# main.net
KiCad netlist of a schematic drawn in EAGLE
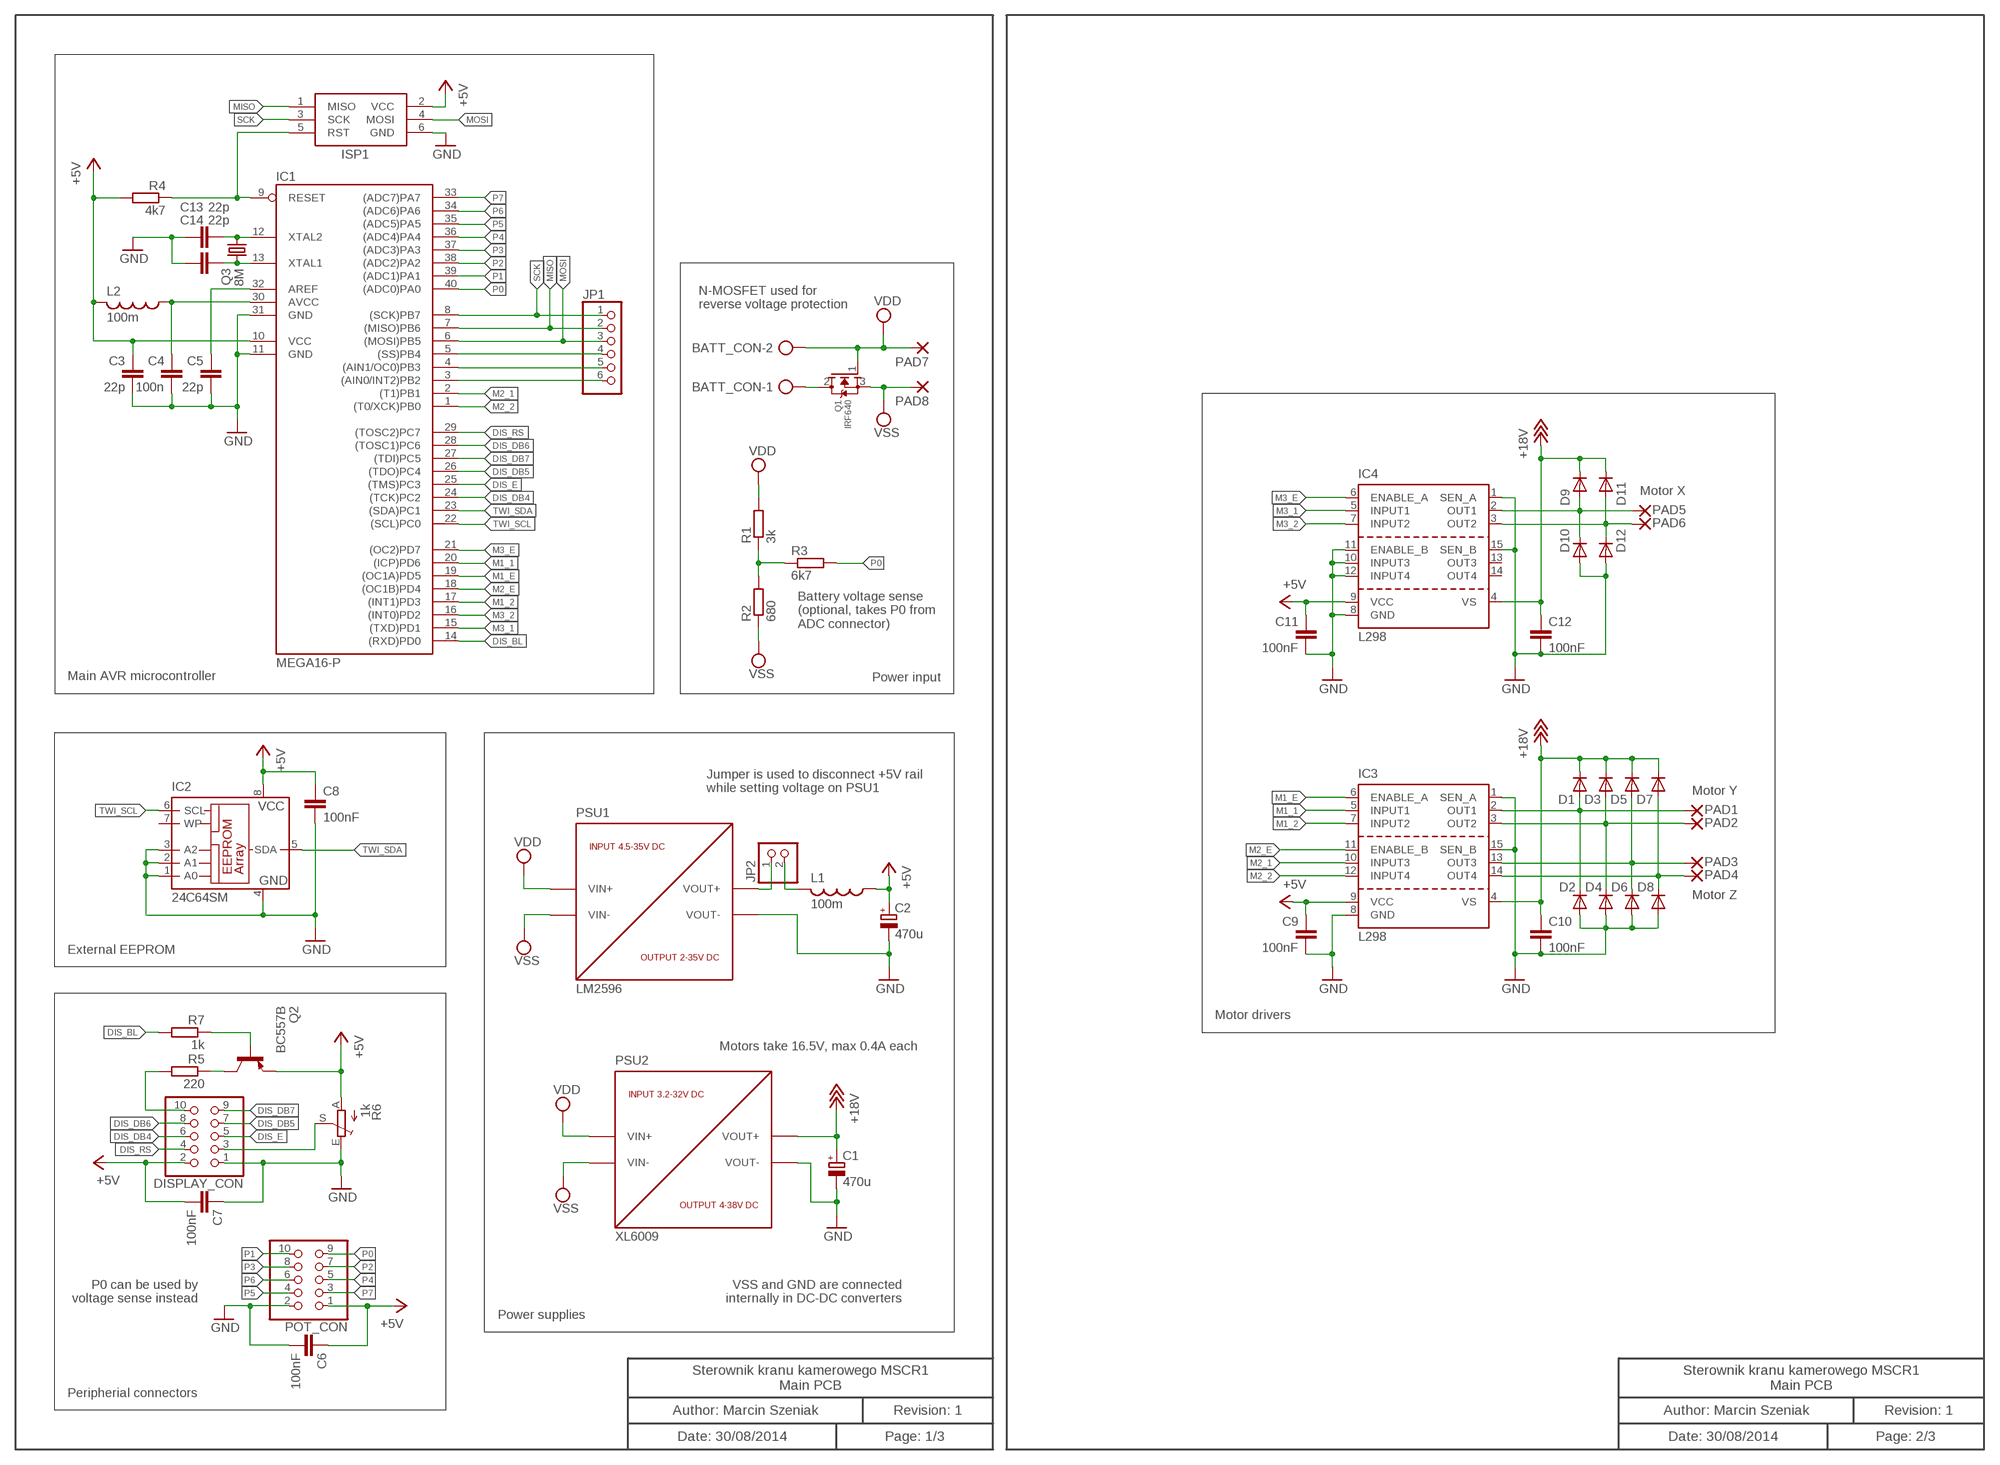
[diagram p0: schematic, sheet 1]

(export (version "E")
  (design (tool "Eeschema 10.0.6"))
  (components
    (comp (ref "BATT_CON")
      (value "AK500/2-H")
      (footprint "eagle-import:AK500_2-H")
      (libsource (lib "eagle-import") (part "AK500/2-H"))
    )
    (comp (ref "C1")
      (value "470u")
      (footprint "eagle-import:E3,5-8")
      (libsource (lib "eagle-import") (part "CPOL-EUE3.5-8"))
    )
    (comp (ref "C2")
      (value "470u")
      (footprint "eagle-import:E5-8,5")
      (libsource (lib "eagle-import") (part "CPOL-EUE5-8.5"))
    )
    (comp (ref "C3")
      (value "22p")
      (footprint "eagle-import:C025-025X050")
      (libsource (lib "eagle-import") (part "C-EU025-025X050"))
    )
    (comp (ref "C4")
      (value "100n")
      (footprint "eagle-import:C025-025X050")
      (libsource (lib "eagle-import") (part "C-EU025-025X050"))
    )
    (comp (ref "C5")
      (value "22p")
      (footprint "eagle-import:C025-025X050")
      (libsource (lib "eagle-import") (part "C-EU025-025X050"))
    )
    (comp (ref "C6")
      (value "100nF")
      (footprint "eagle-import:C025-025X050")
      (libsource (lib "eagle-import") (part "C-EU025-025X050"))
    )
    (comp (ref "C7")
      (value "100nF")
      (footprint "eagle-import:C050-024X044")
      (libsource (lib "eagle-import") (part "C-EU050-024X044"))
    )
    (comp (ref "C8")
      (value "100nF")
      (footprint "eagle-import:C050-024X044")
      (libsource (lib "eagle-import") (part "C-EU050-024X044"))
    )
    (comp (ref "C9")
      (value "100nF")
      (footprint "eagle-import:C075-032X103")
      (libsource (lib "eagle-import") (part "C-EU075-032X103"))
    )
    (comp (ref "C10")
      (value "100nF")
      (footprint "eagle-import:C075-032X103")
      (libsource (lib "eagle-import") (part "C-EU075-032X103"))
    )
    (comp (ref "C11")
      (value "100nF")
      (footprint "eagle-import:C075-032X103")
      (libsource (lib "eagle-import") (part "C-EU075-032X103"))
    )
    (comp (ref "C12")
      (value "100nF")
      (footprint "eagle-import:C075-032X103")
      (libsource (lib "eagle-import") (part "C-EU075-032X103"))
    )
    (comp (ref "C13")
      (value "22p")
      (footprint "eagle-import:C025-025X050")
      (libsource (lib "eagle-import") (part "C-EU025-025X050"))
    )
    (comp (ref "C14")
      (value "22p")
      (footprint "eagle-import:C025-025X050")
      (libsource (lib "eagle-import") (part "C-EU025-025X050"))
    )
    (comp (ref "D1")
      (value "UF4003")
      (footprint "eagle-import:DO41-10")
      (libsource (lib "eagle-import") (part "UF4003"))
    )
    (comp (ref "D2")
      (value "UF4003")
      (footprint "eagle-import:DO41-10")
      (libsource (lib "eagle-import") (part "UF4003"))
    )
    (comp (ref "D3")
      (value "UF4003")
      (footprint "eagle-import:DO41-10")
      (libsource (lib "eagle-import") (part "UF4003"))
    )
    (comp (ref "D4")
      (value "UF4003")
      (footprint "eagle-import:DO41-10")
      (libsource (lib "eagle-import") (part "UF4003"))
    )
    (comp (ref "D5")
      (value "UF4003")
      (footprint "eagle-import:DO41-10")
      (libsource (lib "eagle-import") (part "UF4003"))
    )
    (comp (ref "D6")
      (value "UF4003")
      (footprint "eagle-import:DO41-10")
      (libsource (lib "eagle-import") (part "UF4003"))
    )
    (comp (ref "D7")
      (value "UF4003")
      (footprint "eagle-import:DO41-10")
      (libsource (lib "eagle-import") (part "UF4003"))
    )
    (comp (ref "D8")
      (value "UF4003")
      (footprint "eagle-import:DO41-10")
      (libsource (lib "eagle-import") (part "UF4003"))
    )
    (comp (ref "D9")
      (value "UF4003")
      (footprint "eagle-import:DO41-10")
      (libsource (lib "eagle-import") (part "UF4003"))
    )
    (comp (ref "D10")
      (value "UF4003")
      (footprint "eagle-import:DO41-10")
      (libsource (lib "eagle-import") (part "UF4003"))
    )
    (comp (ref "D11")
      (value "UF4003")
      (footprint "eagle-import:DO41-10")
      (libsource (lib "eagle-import") (part "UF4003"))
    )
    (comp (ref "D12")
      (value "UF4003")
      (footprint "eagle-import:DO41-10")
      (libsource (lib "eagle-import") (part "UF4003"))
    )
    (comp (ref "DISPLAY_CON")
      (value "PINHD-2X5")
      (footprint "eagle-import:2X05")
      (libsource (lib "eagle-import") (part "PINHD-2X5"))
    )
    (comp (ref "IC1")
      (value "MEGA16-P")
      (footprint "eagle-import:DIL40")
      (fields (field (name "MPN") "ATMEGA16-16PU"))
      (libsource (lib "eagle-import") (part "MEGA16-P"))
    )
    (comp (ref "IC2")
      (value "24C64SM")
      (footprint "eagle-import:SO-08M")
      (fields (field (name "MF") "RAMTRON INTERNATIONAL CORP") (field (name "MPN") "FM24C64-S"))
      (libsource (lib "eagle-import") (part "24SMC64"))
    )
    (comp (ref "IC3")
      (value "L298")
      (footprint "eagle-import:MULTIWATT-15")
      (fields (field (name "MPN") "L298N"))
      (libsource (lib "eagle-import") (part "L298"))
    )
    (comp (ref "IC4")
      (value "L298")
      (footprint "eagle-import:MULTIWATT-15")
      (fields (field (name "MPN") "L298N"))
      (libsource (lib "eagle-import") (part "L298"))
    )
    (comp (ref "ISP1")
      (value "AVRISP-6")
      (footprint "eagle-import:AVRISP")
      (libsource (lib "eagle-import") (part "AVRISP-6"))
    )
    (comp (ref "JP1")
      (value "PINHD-1X6")
      (footprint "eagle-import:1X06")
      (libsource (lib "eagle-import") (part "PINHD-1X6"))
    )
    (comp (ref "JP2")
      (value "PINHD-1X2")
      (footprint "eagle-import:1X02")
      (libsource (lib "eagle-import") (part "PINHD-1X2"))
    )
    (comp (ref "L1")
      (value "100m")
      (footprint "eagle-import:0204_7")
      (libsource (lib "eagle-import") (part "L-US0204/7"))
    )
    (comp (ref "L2")
      (value "100m")
      (footprint "eagle-import:0204_7")
      (libsource (lib "eagle-import") (part "L-US0204/7"))
    )
    (comp (ref "PAD1")
      (value "2,54/1,1KLOCWIRE1")
      (footprint "eagle-import:KLOCWIRE1")
      (libsource (lib "eagle-import") (part "2,54/1,1KLOCWIRE1"))
    )
    (comp (ref "PAD2")
      (value "2,54/1,1KLOCWIRE1")
      (footprint "eagle-import:KLOCWIRE1")
      (libsource (lib "eagle-import") (part "2,54/1,1KLOCWIRE1"))
    )
    (comp (ref "PAD3")
      (value "2,54/1,1KLOCWIRE1")
      (footprint "eagle-import:KLOCWIRE1")
      (libsource (lib "eagle-import") (part "2,54/1,1KLOCWIRE1"))
    )
    (comp (ref "PAD4")
      (value "2,54/1,1KLOCWIRE1")
      (footprint "eagle-import:KLOCWIRE1")
      (libsource (lib "eagle-import") (part "2,54/1,1KLOCWIRE1"))
    )
    (comp (ref "PAD5")
      (value "2,54/1,1KLOCWIRE1")
      (footprint "eagle-import:KLOCWIRE1")
      (libsource (lib "eagle-import") (part "2,54/1,1KLOCWIRE1"))
    )
    (comp (ref "PAD6")
      (value "2,54/1,1KLOCWIRE1")
      (footprint "eagle-import:KLOCWIRE1")
      (libsource (lib "eagle-import") (part "2,54/1,1KLOCWIRE1"))
    )
    (comp (ref "PAD7")
      (value "2,54/1,1KLOCWIRE1")
      (footprint "eagle-import:KLOCWIRE1")
      (libsource (lib "eagle-import") (part "2,54/1,1KLOCWIRE1"))
    )
    (comp (ref "PAD8")
      (value "2,54/1,1KLOCWIRE1")
      (footprint "eagle-import:KLOCWIRE1")
      (libsource (lib "eagle-import") (part "2,54/1,1KLOCWIRE1"))
    )
    (comp (ref "POT_CON")
      (value "PINHD-2X5")
      (footprint "eagle-import:2X05")
      (libsource (lib "eagle-import") (part "PINHD-2X5"))
    )
    (comp (ref "PSU1")
      (value "LM2596")
      (footprint "eagle-import:DC-DC_CONV_MODULE")
      (libsource (lib "eagle-import") (part "DC-DC_CONV_DN"))
    )
    (comp (ref "PSU2")
      (value "XL6009")
      (footprint "eagle-import:DC-DC_CONV_MODULE")
      (libsource (lib "eagle-import") (part "DC-DC_CONV_UP"))
    )
    (comp (ref "Q1")
      (value "IRF640")
      (footprint "eagle-import:TO220V")
      (libsource (lib "eagle-import") (part "MOSFET-NGDS_TO220V"))
    )
    (comp (ref "Q2")
      (value "BC557B")
      (footprint "eagle-import:TO92-EBC")
      (libsource (lib "eagle-import") (part "BC557B"))
    )
    (comp (ref "Q3")
      (value "8M")
      (footprint "eagle-import:TC26V")
      (libsource (lib "eagle-import") (part "CRYSTALTC26V"))
    )
    (comp (ref "R1")
      (value "3k")
      (footprint "eagle-import:0204_7")
      (libsource (lib "eagle-import") (part "R-EU_0204/7"))
    )
    (comp (ref "R2")
      (value "680")
      (footprint "eagle-import:0204_7")
      (libsource (lib "eagle-import") (part "R-EU_0204/7"))
    )
    (comp (ref "R3")
      (value "6k7")
      (footprint "eagle-import:0204_5")
      (libsource (lib "eagle-import") (part "R-EU_0204/5"))
    )
    (comp (ref "R4")
      (value "4k7")
      (footprint "eagle-import:0204_5")
      (libsource (lib "eagle-import") (part "R-EU_0204/5"))
    )
    (comp (ref "R5")
      (value "220")
      (footprint "eagle-import:0204_7")
      (libsource (lib "eagle-import") (part "R-EU_0204/7"))
    )
    (comp (ref "R6")
      (value "1k")
      (footprint "eagle-import:CA6V")
      (libsource (lib "eagle-import") (part "TRIM_EU-CA6V"))
    )
    (comp (ref "R7")
      (value "1k")
      (footprint "eagle-import:0204_7")
      (libsource (lib "eagle-import") (part "R-EU_0204/7"))
    )
  )
  (nets
    (net (code "1") (name "+5V") (class "Default")
      (node (ref "C11") (pin "1") (pinfunction "1_1") (pintype "passive"))
      (node (ref "C2") (pin "+") (pinfunction "+_+") (pintype "passive"))
      (node (ref "C3") (pin "1") (pinfunction "1_1") (pintype "passive"))
      (node (ref "C6") (pin "1") (pinfunction "1_1") (pintype "passive"))
      (node (ref "C7") (pin "2") (pinfunction "2_2") (pintype "passive"))
      (node (ref "C8") (pin "1") (pinfunction "1_1") (pintype "passive"))
      (node (ref "C9") (pin "1") (pinfunction "1_1") (pintype "passive"))
      (node (ref "DISPLAY_CON") (pin "2") (pinfunction "2_2") (pintype "passive"))
      (node (ref "IC1") (pin "10") (pinfunction "VCC_10") (pintype "power_in"))
      (node (ref "IC2") (pin "8") (pinfunction "VCC_8") (pintype "power_in"))
      (node (ref "IC3") (pin "9") (pinfunction "VCC_9") (pintype "power_in"))
      (node (ref "IC4") (pin "9") (pinfunction "VCC_9") (pintype "power_in"))
      (node (ref "ISP1") (pin "2") (pinfunction "VCC_2") (pintype "power_in"))
      (node (ref "L1") (pin "1") (pinfunction "1_1") (pintype "passive"))
      (node (ref "L2") (pin "2") (pinfunction "2_2") (pintype "passive"))
      (node (ref "POT_CON") (pin "1") (pinfunction "1_1") (pintype "passive"))
      (node (ref "Q2") (pin "E") (pinfunction "E_E") (pintype "passive"))
      (node (ref "R4") (pin "2") (pinfunction "2_2") (pintype "passive"))
      (node (ref "R6") (pin "A") (pinfunction "A_A") (pintype "passive"))
    )
    (net (code "2") (name "+18V") (class "Default")
      (node (ref "C1") (pin "+") (pinfunction "+_+") (pintype "passive"))
      (node (ref "C10") (pin "1") (pinfunction "1_1") (pintype "passive"))
      (node (ref "C12") (pin "1") (pinfunction "1_1") (pintype "passive"))
      (node (ref "D1") (pin "C") (pinfunction "C_C") (pintype "passive"))
      (node (ref "D11") (pin "C") (pinfunction "C_C") (pintype "passive"))
      (node (ref "D3") (pin "C") (pinfunction "C_C") (pintype "passive"))
      (node (ref "D5") (pin "C") (pinfunction "C_C") (pintype "passive"))
      (node (ref "D7") (pin "C") (pinfunction "C_C") (pintype "passive"))
      (node (ref "D9") (pin "C") (pinfunction "C_C") (pintype "passive"))
      (node (ref "IC3") (pin "4") (pinfunction "VS_4") (pintype "power_in"))
      (node (ref "IC4") (pin "4") (pinfunction "VS_4") (pintype "power_in"))
      (node (ref "PSU2") (pin "OUT+") (pinfunction "VOUT+_OUT+") (pintype "power_in"))
    )
    (net (code "3") (name "DIS_BL") (class "Default")
      (node (ref "IC1") (pin "14") (pinfunction "(RXD)PD0_14") (pintype "bidirectional"))
      (node (ref "R7") (pin "2") (pinfunction "2_2") (pintype "passive"))
    )
    (net (code "4") (name "DIS_DB4") (class "Default")
      (node (ref "DISPLAY_CON") (pin "6") (pinfunction "6_6") (pintype "passive"))
      (node (ref "IC1") (pin "24") (pinfunction "(TCK)PC2_24") (pintype "bidirectional"))
    )
    (net (code "5") (name "DIS_DB5") (class "Default")
      (node (ref "DISPLAY_CON") (pin "7") (pinfunction "7_7") (pintype "passive"))
      (node (ref "IC1") (pin "26") (pinfunction "(TDO)PC4_26") (pintype "bidirectional"))
    )
    (net (code "6") (name "DIS_DB6") (class "Default")
      (node (ref "DISPLAY_CON") (pin "8") (pinfunction "8_8") (pintype "passive"))
      (node (ref "IC1") (pin "28") (pinfunction "(TOSC1)PC6_28") (pintype "bidirectional"))
    )
    (net (code "7") (name "DIS_DB7") (class "Default")
      (node (ref "DISPLAY_CON") (pin "9") (pinfunction "9_9") (pintype "passive"))
      (node (ref "IC1") (pin "27") (pinfunction "(TDI)PC5_27") (pintype "bidirectional"))
    )
    (net (code "8") (name "DIS_E") (class "Default")
      (node (ref "DISPLAY_CON") (pin "5") (pinfunction "5_5") (pintype "passive"))
      (node (ref "IC1") (pin "25") (pinfunction "(TMS)PC3_25") (pintype "bidirectional"))
    )
    (net (code "9") (name "DIS_RS") (class "Default")
      (node (ref "DISPLAY_CON") (pin "4") (pinfunction "4_4") (pintype "passive"))
      (node (ref "IC1") (pin "29") (pinfunction "(TOSC2)PC7_29") (pintype "bidirectional"))
    )
    (net (code "10") (name "GND") (class "Default")
      (node (ref "C1") (pin "-") (pinfunction "-_-") (pintype "passive"))
      (node (ref "C10") (pin "2") (pinfunction "2_2") (pintype "passive"))
      (node (ref "C11") (pin "2") (pinfunction "2_2") (pintype "passive"))
      (node (ref "C12") (pin "2") (pinfunction "2_2") (pintype "passive"))
      (node (ref "C13") (pin "2") (pinfunction "2_2") (pintype "passive"))
      (node (ref "C14") (pin "2") (pinfunction "2_2") (pintype "passive"))
      (node (ref "C2") (pin "-") (pinfunction "-_-") (pintype "passive"))
      (node (ref "C3") (pin "2") (pinfunction "2_2") (pintype "passive"))
      (node (ref "C4") (pin "2") (pinfunction "2_2") (pintype "passive"))
      (node (ref "C5") (pin "2") (pinfunction "2_2") (pintype "passive"))
      (node (ref "C6") (pin "2") (pinfunction "2_2") (pintype "passive"))
      (node (ref "C7") (pin "1") (pinfunction "1_1") (pintype "passive"))
      (node (ref "C8") (pin "2") (pinfunction "2_2") (pintype "passive"))
      (node (ref "C9") (pin "2") (pinfunction "2_2") (pintype "passive"))
      (node (ref "D10") (pin "A") (pinfunction "A_A") (pintype "passive"))
      (node (ref "D12") (pin "A") (pinfunction "A_A") (pintype "passive"))
      (node (ref "D2") (pin "A") (pinfunction "A_A") (pintype "passive"))
      (node (ref "D4") (pin "A") (pinfunction "A_A") (pintype "passive"))
      (node (ref "D6") (pin "A") (pinfunction "A_A") (pintype "passive"))
      (node (ref "D8") (pin "A") (pinfunction "A_A") (pintype "passive"))
      (node (ref "DISPLAY_CON") (pin "1") (pinfunction "1_1") (pintype "passive"))
      (node (ref "IC1") (pin "11") (pinfunction "GND_11") (pintype "power_in"))
      (node (ref "IC1") (pin "31") (pinfunction "GND_31") (pintype "power_in"))
      (node (ref "IC2") (pin "1") (pinfunction "A0_1") (pintype "input"))
      (node (ref "IC2") (pin "2") (pinfunction "A1_2") (pintype "input"))
      (node (ref "IC2") (pin "3") (pinfunction "A2_3") (pintype "input"))
      (node (ref "IC2") (pin "4") (pinfunction "GND_4") (pintype "power_in"))
      (node (ref "IC3") (pin "1") (pinfunction "SEN_A_1") (pintype "input"))
      (node (ref "IC3") (pin "15") (pinfunction "SEN_B_15") (pintype "input"))
      (node (ref "IC3") (pin "8") (pinfunction "GND_8") (pintype "power_in"))
      (node (ref "IC4") (pin "1") (pinfunction "SEN_A_1") (pintype "input"))
      (node (ref "IC4") (pin "10") (pinfunction "INPUT3_10") (pintype "input"))
      (node (ref "IC4") (pin "11") (pinfunction "ENABLE_B_11") (pintype "input"))
      (node (ref "IC4") (pin "12") (pinfunction "INPUT4_12") (pintype "input"))
      (node (ref "IC4") (pin "15") (pinfunction "SEN_B_15") (pintype "input"))
      (node (ref "IC4") (pin "8") (pinfunction "GND_8") (pintype "power_in"))
      (node (ref "ISP1") (pin "6") (pinfunction "GND_6") (pintype "power_in"))
      (node (ref "POT_CON") (pin "2") (pinfunction "2_2") (pintype "passive"))
      (node (ref "PSU1") (pin "OUT-") (pinfunction "VOUT-_OUT-") (pintype "power_in"))
      (node (ref "PSU2") (pin "OUT-") (pinfunction "VOUT-_OUT-") (pintype "power_in"))
      (node (ref "R6") (pin "E") (pinfunction "E_E") (pintype "passive"))
    )
    (net (code "11") (name "M1_1") (class "Default")
      (node (ref "IC1") (pin "20") (pinfunction "(ICP)PD6_20") (pintype "bidirectional"))
      (node (ref "IC3") (pin "5") (pinfunction "INPUT1_5") (pintype "input"))
    )
    (net (code "12") (name "M1_2") (class "Default")
      (node (ref "IC1") (pin "17") (pinfunction "(INT1)PD3_17") (pintype "bidirectional"))
      (node (ref "IC3") (pin "7") (pinfunction "INPUT2_7") (pintype "input"))
    )
    (net (code "13") (name "M1_E") (class "Default")
      (node (ref "IC1") (pin "19") (pinfunction "(OC1A)PD5_19") (pintype "bidirectional"))
      (node (ref "IC3") (pin "6") (pinfunction "ENABLE_A_6") (pintype "input"))
    )
    (net (code "14") (name "M2_1") (class "Default")
      (node (ref "IC1") (pin "2") (pinfunction "(T1)PB1_2") (pintype "bidirectional"))
      (node (ref "IC3") (pin "10") (pinfunction "INPUT3_10") (pintype "input"))
    )
    (net (code "15") (name "M2_2") (class "Default")
      (node (ref "IC1") (pin "1") (pinfunction "(T0/XCK)PB0_1") (pintype "bidirectional"))
      (node (ref "IC3") (pin "12") (pinfunction "INPUT4_12") (pintype "input"))
    )
    (net (code "16") (name "M2_E") (class "Default")
      (node (ref "IC1") (pin "18") (pinfunction "(OC1B)PD4_18") (pintype "bidirectional"))
      (node (ref "IC3") (pin "11") (pinfunction "ENABLE_B_11") (pintype "input"))
    )
    (net (code "17") (name "M3_1") (class "Default")
      (node (ref "IC1") (pin "15") (pinfunction "(TXD)PD1_15") (pintype "bidirectional"))
      (node (ref "IC4") (pin "5") (pinfunction "INPUT1_5") (pintype "input"))
    )
    (net (code "18") (name "M3_2") (class "Default")
      (node (ref "IC1") (pin "16") (pinfunction "(INT0)PD2_16") (pintype "bidirectional"))
      (node (ref "IC4") (pin "7") (pinfunction "INPUT2_7") (pintype "input"))
    )
    (net (code "19") (name "M3_E") (class "Default")
      (node (ref "IC1") (pin "21") (pinfunction "(OC2)PD7_21") (pintype "bidirectional"))
      (node (ref "IC4") (pin "6") (pinfunction "ENABLE_A_6") (pintype "input"))
    )
    (net (code "20") (name "MISO") (class "Default")
      (node (ref "IC1") (pin "7") (pinfunction "(MISO)PB6_7") (pintype "bidirectional"))
      (node (ref "ISP1") (pin "1") (pinfunction "MISO_1") (pintype "input"))
      (node (ref "JP1") (pin "2") (pinfunction "2_2") (pintype "passive"))
    )
    (net (code "21") (name "MOSI") (class "Default")
      (node (ref "IC1") (pin "6") (pinfunction "(MOSI)PB5_6") (pintype "bidirectional"))
      (node (ref "ISP1") (pin "4") (pinfunction "MOSI_4") (pintype "output"))
      (node (ref "JP1") (pin "3") (pinfunction "3_3") (pintype "passive"))
    )
    (net (code "22") (name "Net-(BATT_CONA-KL)") (class "Default")
      (node (ref "BATT_CON") (pin "1") (pinfunction "KL_1") (pintype "passive"))
      (node (ref "Q1") (pin "2") (pinfunction "D_2") (pintype "bidirectional"))
    )
    (net (code "23") (name "Net-(DISPLAY_CON-Pad3)") (class "Default")
      (node (ref "DISPLAY_CON") (pin "3") (pinfunction "3_3") (pintype "passive"))
      (node (ref "R6") (pin "S") (pinfunction "S_S") (pintype "passive"))
    )
    (net (code "24") (name "Net-(DISPLAY_CON-Pad10)") (class "Default")
      (node (ref "DISPLAY_CON") (pin "10") (pinfunction "10_10") (pintype "passive"))
      (node (ref "R5") (pin "2") (pinfunction "2_2") (pintype "passive"))
    )
    (net (code "25") (name "Net-(IC1-(AIN0{slash}INT2)PB2)") (class "Default")
      (node (ref "IC1") (pin "3") (pinfunction "(AIN0/INT2)PB2_3") (pintype "bidirectional"))
      (node (ref "JP1") (pin "6") (pinfunction "6_6") (pintype "passive"))
    )
    (net (code "26") (name "Net-(IC1-(AIN1{slash}OC0)PB3)") (class "Default")
      (node (ref "IC1") (pin "4") (pinfunction "(AIN1/OC0)PB3_4") (pintype "bidirectional"))
      (node (ref "JP1") (pin "5") (pinfunction "5_5") (pintype "passive"))
    )
    (net (code "27") (name "Net-(IC1-(SS)PB4)") (class "Default")
      (node (ref "IC1") (pin "5") (pinfunction "(SS)PB4_5") (pintype "bidirectional"))
      (node (ref "JP1") (pin "4") (pinfunction "4_4") (pintype "passive"))
    )
    (net (code "28") (name "Net-(IC1-AREF)") (class "Default")
      (node (ref "C5") (pin "1") (pinfunction "1_1") (pintype "passive"))
      (node (ref "IC1") (pin "32") (pinfunction "AREF_32") (pintype "passive"))
    )
    (net (code "29") (name "Net-(IC1-AVCC)") (class "Default")
      (node (ref "C4") (pin "1") (pinfunction "1_1") (pintype "passive"))
      (node (ref "IC1") (pin "30") (pinfunction "AVCC_30") (pintype "power_in"))
      (node (ref "L2") (pin "1") (pinfunction "1_1") (pintype "passive"))
    )
    (net (code "30") (name "Net-(IC1-RESET)") (class "Default")
      (node (ref "IC1") (pin "9") (pinfunction "RESET_9") (pintype "input"))
      (node (ref "ISP1") (pin "5") (pinfunction "RST_5") (pintype "output"))
      (node (ref "R4") (pin "1") (pinfunction "1_1") (pintype "passive"))
    )
    (net (code "31") (name "Net-(IC1-XTAL1)") (class "Default")
      (node (ref "C14") (pin "1") (pinfunction "1_1") (pintype "passive"))
      (node (ref "IC1") (pin "13") (pinfunction "XTAL1_13") (pintype "bidirectional"))
      (node (ref "Q3") (pin "1") (pinfunction "1_1") (pintype "passive"))
    )
    (net (code "32") (name "Net-(IC1-XTAL2)") (class "Default")
      (node (ref "C13") (pin "1") (pinfunction "1_1") (pintype "passive"))
      (node (ref "IC1") (pin "12") (pinfunction "XTAL2_12") (pintype "bidirectional"))
      (node (ref "Q3") (pin "2") (pinfunction "2_2") (pintype "passive"))
    )
    (net (code "33") (name "Net-(IC3-OUT1)") (class "Default")
      (node (ref "D1") (pin "A") (pinfunction "A_A") (pintype "passive"))
      (node (ref "D2") (pin "C") (pinfunction "C_C") (pintype "passive"))
      (node (ref "IC3") (pin "2") (pinfunction "OUT1_2") (pintype "output"))
      (node (ref "PAD1") (pin "1") (pinfunction "P_1") (pintype "passive"))
    )
    (net (code "34") (name "Net-(IC3-OUT2)") (class "Default")
      (node (ref "D3") (pin "A") (pinfunction "A_A") (pintype "passive"))
      (node (ref "D4") (pin "C") (pinfunction "C_C") (pintype "passive"))
      (node (ref "IC3") (pin "3") (pinfunction "OUT2_3") (pintype "output"))
      (node (ref "PAD2") (pin "1") (pinfunction "P_1") (pintype "passive"))
    )
    (net (code "35") (name "Net-(IC3-OUT3)") (class "Default")
      (node (ref "D5") (pin "A") (pinfunction "A_A") (pintype "passive"))
      (node (ref "D6") (pin "C") (pinfunction "C_C") (pintype "passive"))
      (node (ref "IC3") (pin "13") (pinfunction "OUT3_13") (pintype "output"))
      (node (ref "PAD3") (pin "1") (pinfunction "P_1") (pintype "passive"))
    )
    (net (code "36") (name "Net-(IC3-OUT4)") (class "Default")
      (node (ref "D7") (pin "A") (pinfunction "A_A") (pintype "passive"))
      (node (ref "D8") (pin "C") (pinfunction "C_C") (pintype "passive"))
      (node (ref "IC3") (pin "14") (pinfunction "OUT4_14") (pintype "output"))
      (node (ref "PAD4") (pin "1") (pinfunction "P_1") (pintype "passive"))
    )
    (net (code "37") (name "Net-(IC4-OUT1)") (class "Default")
      (node (ref "D10") (pin "C") (pinfunction "C_C") (pintype "passive"))
      (node (ref "D9") (pin "A") (pinfunction "A_A") (pintype "passive"))
      (node (ref "IC4") (pin "2") (pinfunction "OUT1_2") (pintype "output"))
      (node (ref "PAD5") (pin "1") (pinfunction "P_1") (pintype "passive"))
    )
    (net (code "38") (name "Net-(IC4-OUT2)") (class "Default")
      (node (ref "D11") (pin "A") (pinfunction "A_A") (pintype "passive"))
      (node (ref "D12") (pin "C") (pinfunction "C_C") (pintype "passive"))
      (node (ref "IC4") (pin "3") (pinfunction "OUT2_3") (pintype "output"))
      (node (ref "PAD6") (pin "1") (pinfunction "P_1") (pintype "passive"))
    )
    (net (code "39") (name "Net-(JP2-Pad2)") (class "Default")
      (node (ref "JP2") (pin "2") (pinfunction "2_2") (pintype "passive"))
      (node (ref "L1") (pin "2") (pinfunction "2_2") (pintype "passive"))
    )
    (net (code "40") (name "Net-(PSU1-VOUT+)") (class "Default")
      (node (ref "JP2") (pin "1") (pinfunction "1_1") (pintype "passive"))
      (node (ref "PSU1") (pin "OUT+") (pinfunction "VOUT+_OUT+") (pintype "power_in"))
    )
    (net (code "41") (name "Net-(Q2-PadB)") (class "Default")
      (node (ref "Q2") (pin "B") (pinfunction "B_B") (pintype "passive"))
      (node (ref "R7") (pin "1") (pinfunction "1_1") (pintype "passive"))
    )
    (net (code "42") (name "Net-(Q2-PadC)") (class "Default")
      (node (ref "Q2") (pin "C") (pinfunction "C_C") (pintype "passive"))
      (node (ref "R5") (pin "1") (pinfunction "1_1") (pintype "passive"))
    )
    (net (code "43") (name "Net-(R1-Pad1)") (class "Default")
      (node (ref "R1") (pin "1") (pinfunction "1_1") (pintype "passive"))
      (node (ref "R2") (pin "2") (pinfunction "2_2") (pintype "passive"))
      (node (ref "R3") (pin "1") (pinfunction "1_1") (pintype "passive"))
    )
    (net (code "44") (name "P0") (class "Default")
      (node (ref "IC1") (pin "40") (pinfunction "(ADC0)PA0_40") (pintype "bidirectional"))
      (node (ref "POT_CON") (pin "9") (pinfunction "9_9") (pintype "passive"))
      (node (ref "R3") (pin "2") (pinfunction "2_2") (pintype "passive"))
    )
    (net (code "45") (name "P1") (class "Default")
      (node (ref "IC1") (pin "39") (pinfunction "(ADC1)PA1_39") (pintype "bidirectional"))
      (node (ref "POT_CON") (pin "10") (pinfunction "10_10") (pintype "passive"))
    )
    (net (code "46") (name "P2") (class "Default")
      (node (ref "IC1") (pin "38") (pinfunction "(ADC2)PA2_38") (pintype "bidirectional"))
      (node (ref "POT_CON") (pin "7") (pinfunction "7_7") (pintype "passive"))
    )
    (net (code "47") (name "P3") (class "Default")
      (node (ref "IC1") (pin "37") (pinfunction "(ADC3)PA3_37") (pintype "bidirectional"))
      (node (ref "POT_CON") (pin "8") (pinfunction "8_8") (pintype "passive"))
    )
    (net (code "48") (name "P4") (class "Default")
      (node (ref "IC1") (pin "36") (pinfunction "(ADC4)PA4_36") (pintype "bidirectional"))
      (node (ref "POT_CON") (pin "5") (pinfunction "5_5") (pintype "passive"))
    )
    (net (code "49") (name "P5") (class "Default")
      (node (ref "IC1") (pin "35") (pinfunction "(ADC5)PA5_35") (pintype "bidirectional"))
      (node (ref "POT_CON") (pin "4") (pinfunction "4_4") (pintype "passive"))
    )
    (net (code "50") (name "P6") (class "Default")
      (node (ref "IC1") (pin "34") (pinfunction "(ADC6)PA6_34") (pintype "bidirectional"))
      (node (ref "POT_CON") (pin "6") (pinfunction "6_6") (pintype "passive"))
    )
    (net (code "51") (name "P7") (class "Default")
      (node (ref "IC1") (pin "33") (pinfunction "(ADC7)PA7_33") (pintype "bidirectional"))
      (node (ref "POT_CON") (pin "3") (pinfunction "3_3") (pintype "passive"))
    )
    (net (code "52") (name "SCK") (class "Default")
      (node (ref "IC1") (pin "8") (pinfunction "(SCK)PB7_8") (pintype "bidirectional"))
      (node (ref "ISP1") (pin "3") (pinfunction "SCK_3") (pintype "output"))
      (node (ref "JP1") (pin "1") (pinfunction "1_1") (pintype "passive"))
    )
    (net (code "53") (name "TWI_SCL") (class "Default")
      (node (ref "IC1") (pin "22") (pinfunction "(SCL)PC0_22") (pintype "bidirectional"))
      (node (ref "IC2") (pin "6") (pinfunction "SCL_6") (pintype "input"))
    )
    (net (code "54") (name "TWI_SDA") (class "Default")
      (node (ref "IC1") (pin "23") (pinfunction "(SDA)PC1_23") (pintype "bidirectional"))
      (node (ref "IC2") (pin "5") (pinfunction "SDA_5") (pintype "bidirectional"))
    )
    (net (code "55") (name "VDD") (class "Default")
      (node (ref "BATT_CON") (pin "2") (pinfunction "KL_2") (pintype "passive"))
      (node (ref "PAD7") (pin "1") (pinfunction "P_1") (pintype "passive"))
      (node (ref "PSU1") (pin "IN+") (pinfunction "VIN+_IN+") (pintype "power_in"))
      (node (ref "PSU2") (pin "IN+") (pinfunction "VIN+_IN+") (pintype "power_in"))
      (node (ref "Q1") (pin "1") (pinfunction "G_1") (pintype "bidirectional"))
      (node (ref "R1") (pin "2") (pinfunction "2_2") (pintype "passive"))
    )
    (net (code "56") (name "VSS") (class "Default")
      (node (ref "PAD8") (pin "1") (pinfunction "P_1") (pintype "passive"))
      (node (ref "PSU1") (pin "IN-") (pinfunction "VIN-_IN-") (pintype "power_in"))
      (node (ref "PSU2") (pin "IN-") (pinfunction "VIN-_IN-") (pintype "power_in"))
      (node (ref "Q1") (pin "3") (pinfunction "S_3") (pintype "bidirectional"))
      (node (ref "R2") (pin "1") (pinfunction "1_1") (pintype "passive"))
    )
    (net (code "57") (name "unconnected-(IC2-WP-Pad7)") (class "Default")
      (node (ref "IC2") (pin "7") (pinfunction "WP_7") (pintype "input"))
    )
    (net (code "58") (name "unconnected-(IC4-OUT3-Pad13)") (class "Default")
      (node (ref "IC4") (pin "13") (pinfunction "OUT3_13") (pintype "output"))
    )
    (net (code "59") (name "unconnected-(IC4-OUT4-Pad14)") (class "Default")
      (node (ref "IC4") (pin "14") (pinfunction "OUT4_14") (pintype "output"))
    )
  )
)
